# roboproj2q1.net
KiCad netlist of a schematic drawn in EAGLE
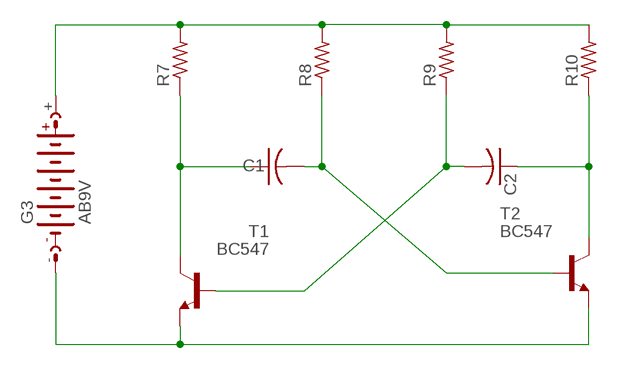
[diagram p0: schematic, sheet 1]

(export (version "E")
  (design (tool "Eeschema 10.0.6"))
  (components
    (comp (ref "C1")
      (value "C-USC0805")
      (footprint "eagle-import:C0805")
      (libsource (lib "eagle-import") (part "C-USC0805"))
    )
    (comp (ref "C2")
      (value "C-USC0805")
      (footprint "eagle-import:C0805")
      (libsource (lib "eagle-import") (part "C-USC0805"))
    )
    (comp (ref "G3")
      (value "AB9V")
      (footprint "eagle-import:AB9V")
      (libsource (lib "eagle-import") (part "AB9V"))
    )
    (comp (ref "R7")
      (value "R-US_R0805")
      (footprint "eagle-import:R0805")
      (libsource (lib "eagle-import") (part "R-US_R0805"))
    )
    (comp (ref "R8")
      (value "R-US_R0805")
      (footprint "eagle-import:R0805")
      (libsource (lib "eagle-import") (part "R-US_R0805"))
    )
    (comp (ref "R9")
      (value "R-US_R0805")
      (footprint "eagle-import:R0805")
      (libsource (lib "eagle-import") (part "R-US_R0805"))
    )
    (comp (ref "R10")
      (value "R-US_R0805")
      (footprint "eagle-import:R0805")
      (libsource (lib "eagle-import") (part "R-US_R0805"))
    )
    (comp (ref "T1")
      (value "BC547")
      (footprint "eagle-import:TO92")
      (libsource (lib "eagle-import") (part "BC547"))
    )
    (comp (ref "T2")
      (value "BC547")
      (footprint "eagle-import:TO92")
      (libsource (lib "eagle-import") (part "BC547"))
    )
  )
  (nets
    (net (code "1") (name "Net-(G3-Pad+)") (class "Default")
      (node (ref "G3") (pin "+") (pinfunction "+_+") (pintype "passive"))
      (node (ref "R10") (pin "2") (pinfunction "2_2") (pintype "passive"))
      (node (ref "R7") (pin "2") (pinfunction "2_2") (pintype "passive"))
      (node (ref "R8") (pin "2") (pinfunction "2_2") (pintype "passive"))
      (node (ref "R9") (pin "2") (pinfunction "2_2") (pintype "passive"))
    )
    (net (code "2") (name "Net-(T1-B)") (class "Default")
      (node (ref "C2") (pin "2") (pinfunction "2_2") (pintype "passive"))
      (node (ref "R9") (pin "1") (pinfunction "1_1") (pintype "passive"))
      (node (ref "T1") (pin "2") (pinfunction "B_2") (pintype "passive"))
    )
    (net (code "3") (name "Net-(T1-C)") (class "Default")
      (node (ref "C1") (pin "1") (pinfunction "1_1") (pintype "passive"))
      (node (ref "R7") (pin "1") (pinfunction "1_1") (pintype "passive"))
      (node (ref "T1") (pin "3") (pinfunction "C_3") (pintype "passive"))
    )
    (net (code "4") (name "Net-(T1-E)") (class "Default")
      (node (ref "G3") (pin "-") (pinfunction "-_-") (pintype "passive"))
      (node (ref "T1") (pin "1") (pinfunction "E_1") (pintype "passive"))
      (node (ref "T2") (pin "1") (pinfunction "E_1") (pintype "passive"))
    )
    (net (code "5") (name "Net-(T2-B)") (class "Default")
      (node (ref "C1") (pin "2") (pinfunction "2_2") (pintype "passive"))
      (node (ref "R8") (pin "1") (pinfunction "1_1") (pintype "passive"))
      (node (ref "T2") (pin "2") (pinfunction "B_2") (pintype "passive"))
    )
    (net (code "6") (name "Net-(T2-C)") (class "Default")
      (node (ref "C2") (pin "1") (pinfunction "1_1") (pintype "passive"))
      (node (ref "R10") (pin "1") (pinfunction "1_1") (pintype "passive"))
      (node (ref "T2") (pin "3") (pinfunction "C_3") (pintype "passive"))
    )
  )
)
